# TP_IHM_CONNECTOR.net
KiCad netlist of a schematic drawn in Altium Designer
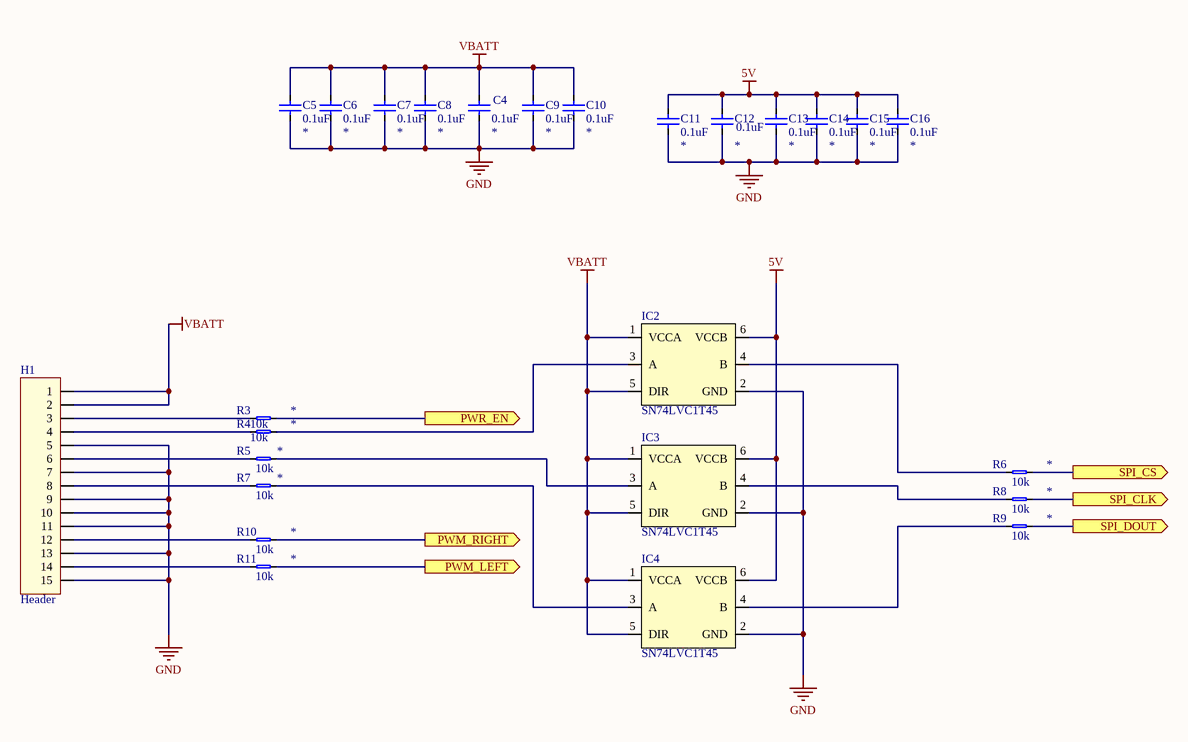
[diagram p0: TP_IHM_CONNECTOR.SchDoc]

(export (version "E")
  (design (tool "Eeschema 10.0.6"))
  (components
    (comp (ref "C4")
      (value "0.1uF")
      (footprint "0402_CAP_LD")
      (description "Ceramic Capacitor")
      (fields (field (name "PACKAGE") "*") (field (name "Comment") "CerCap"))
      (libsource (lib "TpGiven") (part "CerCap"))
    )
    (comp (ref "C5")
      (value "0.1uF")
      (footprint "0603_CAP_LD")
      (description "Ceramic Capacitor")
      (fields (field (name "PACKAGE") "*") (field (name "Comment") "CerCap"))
      (libsource (lib "TpGiven") (part "CerCap"))
    )
    (comp (ref "C6")
      (value "0.1uF")
      (footprint "0603_CAP_LD")
      (description "Ceramic Capacitor")
      (fields (field (name "PACKAGE") "*") (field (name "Comment") "CerCap"))
      (libsource (lib "TpGiven") (part "CerCap"))
    )
    (comp (ref "C7")
      (value "0.1uF")
      (footprint "0603_CAP_LD")
      (description "Ceramic Capacitor")
      (fields (field (name "PACKAGE") "*") (field (name "Comment") "CerCap"))
      (libsource (lib "TpGiven") (part "CerCap"))
    )
    (comp (ref "C8")
      (value "0.1uF")
      (footprint "0603_CAP_LD")
      (description "Ceramic Capacitor")
      (fields (field (name "PACKAGE") "*") (field (name "Comment") "CerCap"))
      (libsource (lib "TpGiven") (part "CerCap"))
    )
    (comp (ref "C9")
      (value "0.1uF")
      (footprint "0402_CAP_LD")
      (description "Ceramic Capacitor")
      (fields (field (name "PACKAGE") "*") (field (name "Comment") "CerCap"))
      (libsource (lib "TpGiven") (part "CerCap"))
    )
    (comp (ref "C10")
      (value "0.1uF")
      (footprint "0402_CAP_LD")
      (description "Ceramic Capacitor")
      (fields (field (name "PACKAGE") "*") (field (name "Comment") "CerCap"))
      (libsource (lib "TpGiven") (part "CerCap"))
    )
    (comp (ref "C11")
      (value "0.1uF")
      (footprint "0603_CAP_LD")
      (description "Ceramic Capacitor")
      (fields (field (name "PACKAGE") "*") (field (name "Comment") "CerCap"))
      (libsource (lib "TpGiven") (part "CerCap"))
    )
    (comp (ref "C12")
      (value "0.1uF")
      (footprint "0603_CAP_LD")
      (description "Ceramic Capacitor")
      (fields (field (name "PACKAGE") "*") (field (name "Comment") "CerCap"))
      (libsource (lib "TpGiven") (part "CerCap"))
    )
    (comp (ref "C13")
      (value "0.1uF")
      (footprint "0603_CAP_LD")
      (description "Ceramic Capacitor")
      (fields (field (name "PACKAGE") "*") (field (name "Comment") "CerCap"))
      (libsource (lib "TpGiven") (part "CerCap"))
    )
    (comp (ref "C14")
      (value "0.1uF")
      (footprint "0402_CAP_LD")
      (description "Ceramic Capacitor")
      (fields (field (name "PACKAGE") "*") (field (name "Comment") "CerCap"))
      (libsource (lib "TpGiven") (part "CerCap"))
    )
    (comp (ref "C15")
      (value "0.1uF")
      (footprint "0402_CAP_LD")
      (description "Ceramic Capacitor")
      (fields (field (name "PACKAGE") "*") (field (name "Comment") "CerCap"))
      (libsource (lib "TpGiven") (part "CerCap"))
    )
    (comp (ref "C16")
      (value "0.1uF")
      (footprint "0402_CAP_LD")
      (description "Ceramic Capacitor")
      (fields (field (name "PACKAGE") "*") (field (name "Comment") "CerCap"))
      (libsource (lib "TpGiven") (part "CerCap"))
    )
    (comp (ref "H1")
      (value "Header")
      (footprint "653115131822")
      (description "Header 15x1")
      (libsource (lib "TpGiven") (part "HEADER_15x1"))
    )
    (comp (ref "IC2")
      (value "SN74LVC1T45")
      (footprint "MO-203AB_LD")
      (description "Single Bit Dual Supply Buffer")
      (libsource (lib "TpGiven") (part "SN74LVC1T45"))
    )
    (comp (ref "IC3")
      (value "SN74LVC1T45")
      (footprint "MO-203AB_LD")
      (description "Single Bit Dual Supply Buffer")
      (libsource (lib "TpGiven") (part "SN74LVC1T45"))
    )
    (comp (ref "IC4")
      (value "SN74LVC1T45")
      (footprint "MO-203AB_LD")
      (description "Single Bit Dual Supply Buffer")
      (libsource (lib "TpGiven") (part "SN74LVC1T45"))
    )
    (comp (ref "R3")
      (value "10k")
      (footprint "0603_RES_LD")
      (description "Resistor")
      (fields (field (name "PACKAGE") "*"))
      (libsource (lib "TpGiven") (part "Resistor"))
    )
    (comp (ref "R4")
      (value "10k")
      (footprint "0603_RES_LD")
      (description "Resistor")
      (fields (field (name "PACKAGE") "*"))
      (libsource (lib "TpGiven") (part "Resistor"))
    )
    (comp (ref "R5")
      (value "10k")
      (footprint "0603_RES_LD")
      (description "Resistor")
      (fields (field (name "PACKAGE") "*"))
      (libsource (lib "TpGiven") (part "Resistor"))
    )
    (comp (ref "R6")
      (value "10k")
      (footprint "0603_RES_LD")
      (description "Resistor")
      (fields (field (name "PACKAGE") "*"))
      (libsource (lib "TpGiven") (part "Resistor"))
    )
    (comp (ref "R7")
      (value "10k")
      (footprint "0603_RES_LD")
      (description "Resistor")
      (fields (field (name "PACKAGE") "*"))
      (libsource (lib "TpGiven") (part "Resistor"))
    )
    (comp (ref "R8")
      (value "10k")
      (footprint "0603_RES_LD")
      (description "Resistor")
      (fields (field (name "PACKAGE") "*"))
      (libsource (lib "TpGiven") (part "Resistor"))
    )
    (comp (ref "R9")
      (value "10k")
      (footprint "0603_RES_LD")
      (description "Resistor")
      (fields (field (name "PACKAGE") "*"))
      (libsource (lib "TpGiven") (part "Resistor"))
    )
    (comp (ref "R10")
      (value "10k")
      (footprint "0603_RES_LD")
      (description "Resistor")
      (fields (field (name "PACKAGE") "*"))
      (libsource (lib "TpGiven") (part "Resistor"))
    )
    (comp (ref "R11")
      (value "10k")
      (footprint "0603_RES_LD")
      (description "Resistor")
      (fields (field (name "PACKAGE") "*"))
      (libsource (lib "TpGiven") (part "Resistor"))
    )
  )
  (nets
    (net (code "1") (name "/PWM_LEFT") (class "Default")
      (node (ref "R11") (pin "2") (pinfunction "2_2") (pintype "passive"))
    )
    (net (code "2") (name "/PWM_RIGHT") (class "Default")
      (node (ref "R10") (pin "2") (pinfunction "2_2") (pintype "passive"))
    )
    (net (code "3") (name "/PWR_EN") (class "Default")
      (node (ref "R3") (pin "2") (pinfunction "2_2") (pintype "passive"))
    )
    (net (code "4") (name "/SPI_CLK") (class "Default")
      (node (ref "R8") (pin "2") (pinfunction "2_2") (pintype "passive"))
    )
    (net (code "5") (name "/SPI_CS") (class "Default")
      (node (ref "R6") (pin "2") (pinfunction "2_2") (pintype "passive"))
    )
    (net (code "6") (name "/SPI_DOUT") (class "Default")
      (node (ref "R9") (pin "2") (pinfunction "2_2") (pintype "passive"))
    )
    (net (code "7") (name "5V") (class "Default")
      (node (ref "C11") (pin "2") (pinfunction "2_2") (pintype "passive"))
      (node (ref "C12") (pin "2") (pinfunction "2_2") (pintype "passive"))
      (node (ref "C13") (pin "2") (pinfunction "2_2") (pintype "passive"))
      (node (ref "C14") (pin "2") (pinfunction "2_2") (pintype "passive"))
      (node (ref "C15") (pin "2") (pinfunction "2_2") (pintype "passive"))
      (node (ref "C16") (pin "2") (pinfunction "2_2") (pintype "passive"))
      (node (ref "IC2") (pin "6") (pinfunction "VCCB_6") (pintype "passive"))
      (node (ref "IC3") (pin "6") (pinfunction "VCCB_6") (pintype "passive"))
      (node (ref "IC4") (pin "6") (pinfunction "VCCB_6") (pintype "passive"))
    )
    (net (code "8") (name "GND") (class "Default")
      (node (ref "C10") (pin "1") (pinfunction "1_1") (pintype "passive"))
      (node (ref "C11") (pin "1") (pinfunction "1_1") (pintype "passive"))
      (node (ref "C12") (pin "1") (pinfunction "1_1") (pintype "passive"))
      (node (ref "C13") (pin "1") (pinfunction "1_1") (pintype "passive"))
      (node (ref "C14") (pin "1") (pinfunction "1_1") (pintype "passive"))
      (node (ref "C15") (pin "1") (pinfunction "1_1") (pintype "passive"))
      (node (ref "C16") (pin "1") (pinfunction "1_1") (pintype "passive"))
      (node (ref "C4") (pin "1") (pinfunction "1_1") (pintype "passive"))
      (node (ref "C5") (pin "2") (pinfunction "2_2") (pintype "passive"))
      (node (ref "C6") (pin "2") (pinfunction "2_2") (pintype "passive"))
      (node (ref "C7") (pin "2") (pinfunction "2_2") (pintype "passive"))
      (node (ref "C8") (pin "1") (pinfunction "1_1") (pintype "passive"))
      (node (ref "C9") (pin "1") (pinfunction "1_1") (pintype "passive"))
      (node (ref "H1") (pin "10") (pinfunction "10_10") (pintype "passive"))
      (node (ref "H1") (pin "11") (pinfunction "11_11") (pintype "passive"))
      (node (ref "H1") (pin "13") (pinfunction "13_13") (pintype "passive"))
      (node (ref "H1") (pin "15") (pinfunction "15_15") (pintype "passive"))
      (node (ref "H1") (pin "5") (pinfunction "5_5") (pintype "passive"))
      (node (ref "H1") (pin "7") (pinfunction "7_7") (pintype "passive"))
      (node (ref "H1") (pin "9") (pinfunction "9_9") (pintype "passive"))
      (node (ref "IC2") (pin "2") (pinfunction "GND_2") (pintype "passive"))
      (node (ref "IC3") (pin "2") (pinfunction "GND_2") (pintype "passive"))
      (node (ref "IC4") (pin "2") (pinfunction "GND_2") (pintype "passive"))
    )
    (net (code "9") (name "Net-(H1-Pad3)") (class "Default")
      (node (ref "H1") (pin "3") (pinfunction "3_3") (pintype "passive"))
      (node (ref "R3") (pin "1") (pinfunction "1_1") (pintype "passive"))
    )
    (net (code "10") (name "Net-(H1-Pad4)") (class "Default")
      (node (ref "H1") (pin "4") (pinfunction "4_4") (pintype "passive"))
      (node (ref "R4") (pin "1") (pinfunction "1_1") (pintype "passive"))
    )
    (net (code "11") (name "Net-(H1-Pad6)") (class "Default")
      (node (ref "H1") (pin "6") (pinfunction "6_6") (pintype "passive"))
      (node (ref "R5") (pin "1") (pinfunction "1_1") (pintype "passive"))
    )
    (net (code "12") (name "Net-(H1-Pad8)") (class "Default")
      (node (ref "H1") (pin "8") (pinfunction "8_8") (pintype "passive"))
      (node (ref "R7") (pin "1") (pinfunction "1_1") (pintype "passive"))
    )
    (net (code "13") (name "Net-(H1-Pad12)") (class "Default")
      (node (ref "H1") (pin "12") (pinfunction "12_12") (pintype "passive"))
      (node (ref "R10") (pin "1") (pinfunction "1_1") (pintype "passive"))
    )
    (net (code "14") (name "Net-(H1-Pad14)") (class "Default")
      (node (ref "H1") (pin "14") (pinfunction "14_14") (pintype "passive"))
      (node (ref "R11") (pin "1") (pinfunction "1_1") (pintype "passive"))
    )
    (net (code "15") (name "Net-(IC2-A)") (class "Default")
      (node (ref "IC2") (pin "3") (pinfunction "A_3") (pintype "passive"))
      (node (ref "R4") (pin "2") (pinfunction "2_2") (pintype "passive"))
    )
    (net (code "16") (name "Net-(IC2-B)") (class "Default")
      (node (ref "IC2") (pin "4") (pinfunction "B_4") (pintype "passive"))
      (node (ref "R6") (pin "1") (pinfunction "1_1") (pintype "passive"))
    )
    (net (code "17") (name "Net-(IC3-A)") (class "Default")
      (node (ref "IC3") (pin "3") (pinfunction "A_3") (pintype "passive"))
      (node (ref "R5") (pin "2") (pinfunction "2_2") (pintype "passive"))
    )
    (net (code "18") (name "Net-(IC3-B)") (class "Default")
      (node (ref "IC3") (pin "4") (pinfunction "B_4") (pintype "passive"))
      (node (ref "R8") (pin "1") (pinfunction "1_1") (pintype "passive"))
    )
    (net (code "19") (name "Net-(IC4-A)") (class "Default")
      (node (ref "IC4") (pin "3") (pinfunction "A_3") (pintype "passive"))
      (node (ref "R7") (pin "2") (pinfunction "2_2") (pintype "passive"))
    )
    (net (code "20") (name "Net-(IC4-B)") (class "Default")
      (node (ref "IC4") (pin "4") (pinfunction "B_4") (pintype "passive"))
      (node (ref "R9") (pin "1") (pinfunction "1_1") (pintype "passive"))
    )
    (net (code "21") (name "VBATT") (class "Default")
      (node (ref "C10") (pin "2") (pinfunction "2_2") (pintype "passive"))
      (node (ref "C4") (pin "2") (pinfunction "2_2") (pintype "passive"))
      (node (ref "C5") (pin "1") (pinfunction "1_1") (pintype "passive"))
      (node (ref "C6") (pin "1") (pinfunction "1_1") (pintype "passive"))
      (node (ref "C7") (pin "1") (pinfunction "1_1") (pintype "passive"))
      (node (ref "C8") (pin "2") (pinfunction "2_2") (pintype "passive"))
      (node (ref "C9") (pin "2") (pinfunction "2_2") (pintype "passive"))
      (node (ref "H1") (pin "1") (pinfunction "1_1") (pintype "passive"))
      (node (ref "H1") (pin "2") (pinfunction "2_2") (pintype "passive"))
      (node (ref "IC2") (pin "1") (pinfunction "VCCA_1") (pintype "passive"))
      (node (ref "IC2") (pin "5") (pinfunction "DIR_5") (pintype "passive"))
      (node (ref "IC3") (pin "1") (pinfunction "VCCA_1") (pintype "passive"))
      (node (ref "IC3") (pin "5") (pinfunction "DIR_5") (pintype "passive"))
      (node (ref "IC4") (pin "1") (pinfunction "VCCA_1") (pintype "passive"))
      (node (ref "IC4") (pin "5") (pinfunction "DIR_5") (pintype "passive"))
    )
  )
)
